# ET-power.net
KiCad netlist of a schematic drawn in Altium Designer
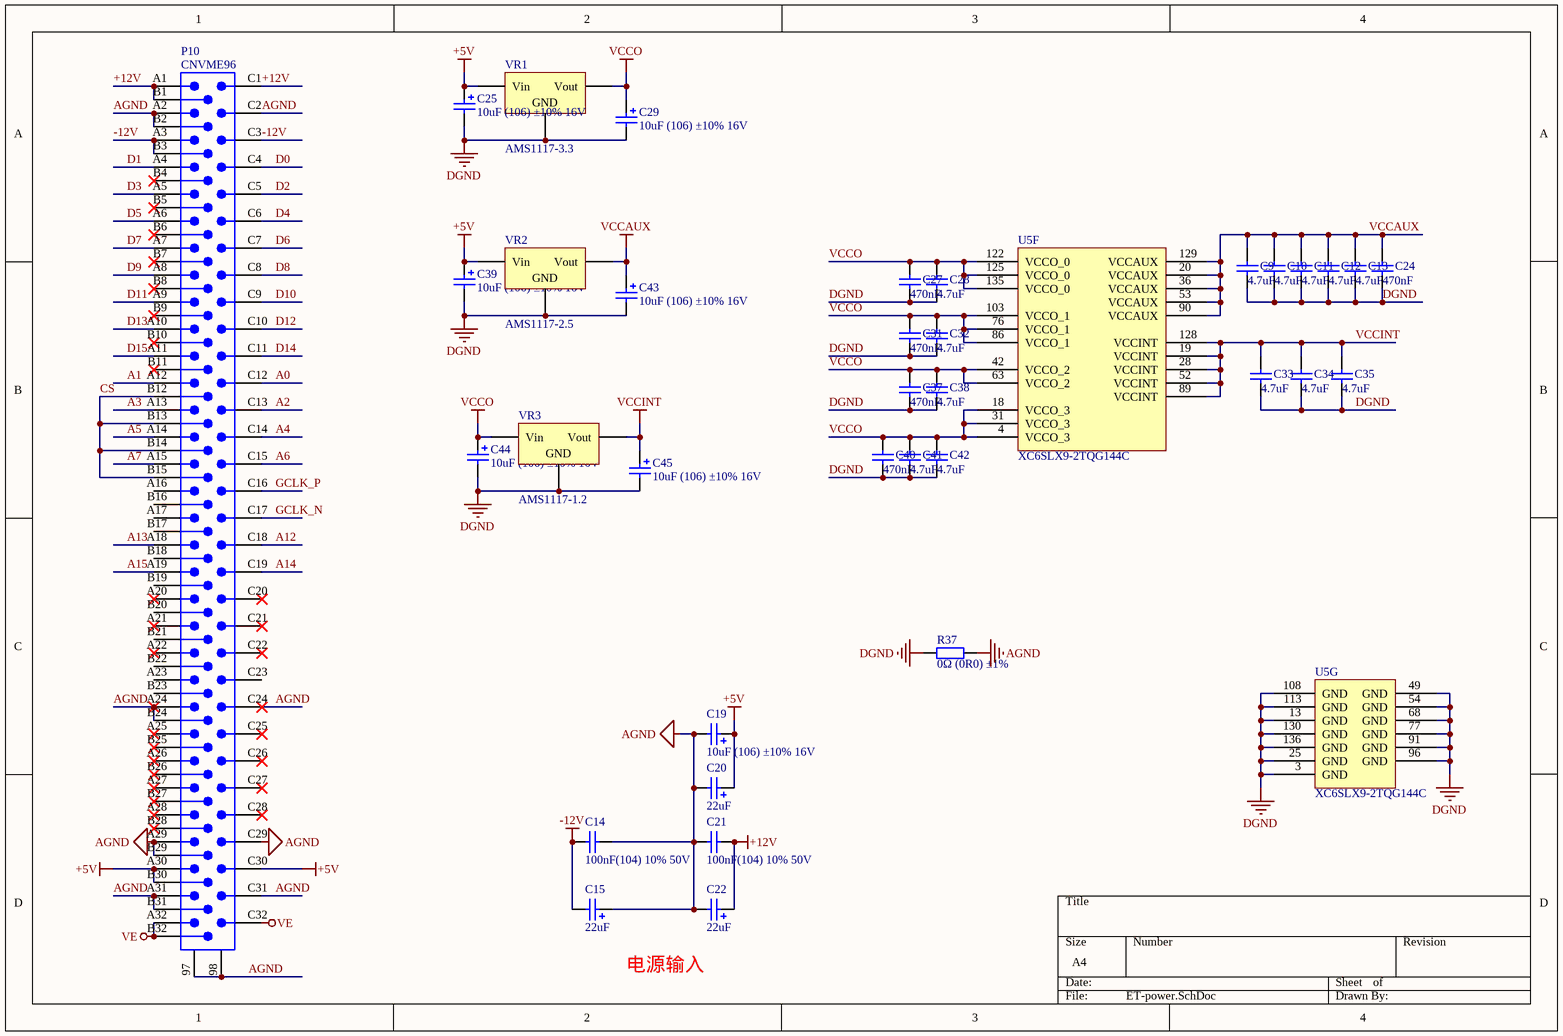
[diagram p0: ET-power.SchDoc]

(export (version "E")
  (design (tool "Eeschema 10.0.6"))
  (components
    (comp (ref "C9")
      (value "4.7uF")
      (footprint "LC-0805_C")
      (description "贴片电容")
      (libsource (lib "Miscellaneous Devices LC") (part "0805 4.7uF (475) 10% 25V"))
    )
    (comp (ref "C10")
      (value "4.7uF")
      (footprint "LC-0805_C")
      (description "贴片电容")
      (libsource (lib "Miscellaneous Devices LC") (part "0805 4.7uF (475) 10% 25V"))
    )
    (comp (ref "C11")
      (value "4.7uF")
      (footprint "LC-0805_C")
      (description "贴片电容")
      (libsource (lib "Miscellaneous Devices LC") (part "0805 4.7uF (475) 10% 25V"))
    )
    (comp (ref "C12")
      (value "4.7uF")
      (footprint "LC-0805_C")
      (description "贴片电容")
      (libsource (lib "Miscellaneous Devices LC") (part "0805 4.7uF (475) 10% 25V"))
    )
    (comp (ref "C13")
      (value "4.7uF")
      (footprint "LC-0805_C")
      (description "贴片电容")
      (libsource (lib "Miscellaneous Devices LC") (part "0805 4.7uF (475) 10% 25V"))
    )
    (comp (ref "C14")
      (value "100nF(104) 10% 50V")
      (footprint "LC-0805_C")
      (description "贴片电容")
      (libsource (lib "Miscellaneous Devices LC") (part "0805 100nF(104) 10% 50V"))
    )
    (comp (ref "C15") (value "22uF") (footprint "CASE-E_7343") (libsource (lib "钽电容") (part "钽电容")))
    (comp (ref "C19")
      (value "10uF (106) ±10% 16V")
      (footprint "LC-CASE-A_3216")
      (description "钽电容")
      (libsource (lib "Miscellaneous Devices LC") (part "3216 10uF (106) 10% 16V"))
    )
    (comp (ref "C20") (value "22uF") (footprint "CASE-E_7343") (libsource (lib "钽电容") (part "钽电容")))
    (comp (ref "C21")
      (value "100nF(104) 10% 50V")
      (footprint "LC-0805_C")
      (description "贴片电容")
      (libsource (lib "Miscellaneous Devices LC") (part "0805 100nF(104) 10% 50V"))
    )
    (comp (ref "C22") (value "22uF") (footprint "CASE-E_7343") (libsource (lib "钽电容") (part "钽电容")))
    (comp (ref "C24")
      (value "470nF")
      (footprint "LC-0805_C")
      (description "贴片电容")
      (libsource (lib "Miscellaneous Devices LC") (part "0805 470nF (474) 10% 50V"))
    )
    (comp (ref "C25")
      (value "10uF (106) ±10% 16V")
      (footprint "LC-CASE-A_3216")
      (description "钽电容")
      (libsource (lib "Miscellaneous Devices LC") (part "3216 10uF (106) 10% 16V"))
    )
    (comp (ref "C27")
      (value "470nF")
      (footprint "LC-0805_C")
      (description "贴片电容")
      (libsource (lib "Miscellaneous Devices LC") (part "0805 470nF (474) 10% 50V"))
    )
    (comp (ref "C28")
      (value "4.7uF")
      (footprint "LC-0805_C")
      (description "贴片电容")
      (libsource (lib "Miscellaneous Devices LC") (part "0805 4.7uF (475) 10% 25V"))
    )
    (comp (ref "C29")
      (value "10uF (106) ±10% 16V")
      (footprint "LC-CASE-A_3216")
      (description "钽电容")
      (libsource (lib "Miscellaneous Devices LC") (part "3216 10uF (106) 10% 16V"))
    )
    (comp (ref "C31")
      (value "470nF")
      (footprint "LC-0805_C")
      (description "贴片电容")
      (libsource (lib "Miscellaneous Devices LC") (part "0805 470nF (474) 10% 50V"))
    )
    (comp (ref "C32")
      (value "4.7uF")
      (footprint "LC-0805_C")
      (description "贴片电容")
      (libsource (lib "Miscellaneous Devices LC") (part "0805 4.7uF (475) 10% 25V"))
    )
    (comp (ref "C33")
      (value "4.7uF")
      (footprint "LC-0805_C")
      (description "贴片电容")
      (libsource (lib "Miscellaneous Devices LC") (part "0805 4.7uF (475) 10% 25V"))
    )
    (comp (ref "C34")
      (value "4.7uF")
      (footprint "LC-0805_C")
      (description "贴片电容")
      (libsource (lib "Miscellaneous Devices LC") (part "0805 4.7uF (475) 10% 25V"))
    )
    (comp (ref "C35")
      (value "4.7uF")
      (footprint "LC-0805_C")
      (description "贴片电容")
      (libsource (lib "Miscellaneous Devices LC") (part "0805 4.7uF (475) 10% 25V"))
    )
    (comp (ref "C37")
      (value "470nF")
      (footprint "LC-0805_C")
      (description "贴片电容")
      (libsource (lib "Miscellaneous Devices LC") (part "0805 470nF (474) 10% 50V"))
    )
    (comp (ref "C38")
      (value "4.7uF")
      (footprint "LC-0805_C")
      (description "贴片电容")
      (libsource (lib "Miscellaneous Devices LC") (part "0805 4.7uF (475) 10% 25V"))
    )
    (comp (ref "C39")
      (value "10uF (106) ±10% 16V")
      (footprint "LC-CASE-A_3216")
      (description "钽电容")
      (libsource (lib "Miscellaneous Devices LC") (part "3216 10uF (106) 10% 16V"))
    )
    (comp (ref "C40")
      (value "470nF")
      (footprint "LC-0805_C")
      (description "贴片电容")
      (libsource (lib "Miscellaneous Devices LC") (part "0805 470nF (474) 10% 50V"))
    )
    (comp (ref "C41")
      (value "4.7uF")
      (footprint "LC-0805_C")
      (description "贴片电容")
      (libsource (lib "Miscellaneous Devices LC") (part "0805 4.7uF (475) 10% 25V"))
    )
    (comp (ref "C42")
      (value "4.7uF")
      (footprint "LC-0805_C")
      (description "贴片电容")
      (libsource (lib "Miscellaneous Devices LC") (part "0805 4.7uF (475) 10% 25V"))
    )
    (comp (ref "C43")
      (value "10uF (106) ±10% 16V")
      (footprint "LC-CASE-A_3216")
      (description "钽电容")
      (libsource (lib "Miscellaneous Devices LC") (part "3216 10uF (106) 10% 16V"))
    )
    (comp (ref "C44")
      (value "10uF (106) ±10% 16V")
      (footprint "LC-CASE-A_3216")
      (description "钽电容")
      (libsource (lib "Miscellaneous Devices LC") (part "3216 10uF (106) 10% 16V"))
    )
    (comp (ref "C45")
      (value "10uF (106) ±10% 16V")
      (footprint "LC-CASE-A_3216")
      (description "钽电容")
      (libsource (lib "Miscellaneous Devices LC") (part "3216 10uF (106) 10% 16V"))
    )
    (comp (ref "P10")
      (value "CNVME96")
      (footprint "CNVME96")
      (description "96-Pin Connector (3x32 2.54mm grid)")
      (libsource (lib "*") (part "CNVME96"))
    )
    (comp (ref "R37")
      (value "0Ω (0R0) ±1%")
      (footprint "LC-0805_R")
      (description "贴片电阻")
      (libsource (lib "Miscellaneous Devices LC") (part "0805 0Ω (0R0) 1%"))
    )
    (comp (ref "U5")
      (value "XC6SLX9-2TQG144C")
      (footprint "TQG144_N")
      (fields (field (name "PUBLISHER") "Altium Limited"))
      (libsource (lib "Xilinx Spartan-6") (part "XC6SLX9-2TQG144C"))
    )
    (comp (ref "VR1")
      (value "AMS1117-3.3")
      (footprint "LC-SOT-223")
      (description "低压差线性稳压(LDO)")
      (libsource (lib "Miscellaneous Devices LC") (part "SOT-223 AMS1117-3.3"))
    )
    (comp (ref "VR2")
      (value "AMS1117-2.5")
      (footprint "LC-SOT-223")
      (description "低压差线性稳压(LDO)")
      (libsource (lib "AMS1117-2.5") (part "SOT-223 AMS1117-2.5"))
    )
    (comp (ref "VR3")
      (value "AMS1117-1.2")
      (footprint "LC-SOT-223")
      (description "低压差线性稳压(LDO)")
      (libsource (lib "AMS1117-1.2") (part "SOT-223 AMS1117-1.2"))
    )
  )
  (nets
    (net (code "1") (name "+5V") (class "Default")
      (node (ref "C19") (pin "1") (pinfunction "1_1") (pintype "passive"))
      (node (ref "C20") (pin "1") (pinfunction "1_1") (pintype "passive"))
      (node (ref "C25") (pin "1") (pinfunction "1_1") (pintype "passive"))
      (node (ref "C39") (pin "1") (pinfunction "1_1") (pintype "passive"))
      (node (ref "P10") (pin "A30") (pinfunction "A30_A30") (pintype "passive"))
      (node (ref "P10") (pin "B30") (pinfunction "B30_B30") (pintype "passive"))
      (node (ref "P10") (pin "C30") (pinfunction "C30_C30") (pintype "passive"))
      (node (ref "VR1") (pin "3") (pinfunction "Vin_3") (pintype "passive"))
      (node (ref "VR2") (pin "3") (pinfunction "Vin_3") (pintype "passive"))
    )
    (net (code "2") (name "+12V") (class "Default")
      (node (ref "C21") (pin "2") (pinfunction "2_2") (pintype "passive"))
      (node (ref "C22") (pin "1") (pinfunction "1_1") (pintype "passive"))
      (node (ref "P10") (pin "A1") (pinfunction "A1_A1") (pintype "passive"))
      (node (ref "P10") (pin "B1") (pinfunction "B1_B1") (pintype "passive"))
      (node (ref "P10") (pin "C1") (pinfunction "C1_C1") (pintype "passive"))
    )
    (net (code "3") (name "-12V") (class "Default")
      (node (ref "C14") (pin "1") (pinfunction "1_1") (pintype "passive"))
      (node (ref "C15") (pin "2") (pinfunction "2_2") (pintype "passive"))
      (node (ref "P10") (pin "A3") (pinfunction "A3_A3") (pintype "passive"))
      (node (ref "P10") (pin "B3") (pinfunction "B3_B3") (pintype "passive"))
      (node (ref "P10") (pin "C3") (pinfunction "C3_C3") (pintype "passive"))
    )
    (net (code "4") (name "/A0") (class "Default")
      (node (ref "P10") (pin "C12") (pinfunction "C12_C12") (pintype "passive"))
    )
    (net (code "5") (name "/A1") (class "Default")
      (node (ref "P10") (pin "A12") (pinfunction "A12_A12") (pintype "passive"))
    )
    (net (code "6") (name "/A2") (class "Default")
      (node (ref "P10") (pin "C13") (pinfunction "C13_C13") (pintype "passive"))
    )
    (net (code "7") (name "/A3") (class "Default")
      (node (ref "P10") (pin "A13") (pinfunction "A13_A13") (pintype "passive"))
    )
    (net (code "8") (name "/A4") (class "Default")
      (node (ref "P10") (pin "C14") (pinfunction "C14_C14") (pintype "passive"))
    )
    (net (code "9") (name "/A5") (class "Default")
      (node (ref "P10") (pin "A14") (pinfunction "A14_A14") (pintype "passive"))
    )
    (net (code "10") (name "/A6") (class "Default")
      (node (ref "P10") (pin "C15") (pinfunction "C15_C15") (pintype "passive"))
    )
    (net (code "11") (name "/A7") (class "Default")
      (node (ref "P10") (pin "A15") (pinfunction "A15_A15") (pintype "passive"))
    )
    (net (code "12") (name "/A12") (class "Default")
      (node (ref "P10") (pin "C18") (pinfunction "C18_C18") (pintype "passive"))
    )
    (net (code "13") (name "/A13") (class "Default")
      (node (ref "P10") (pin "A18") (pinfunction "A18_A18") (pintype "passive"))
    )
    (net (code "14") (name "/A14") (class "Default")
      (node (ref "P10") (pin "C19") (pinfunction "C19_C19") (pintype "passive"))
    )
    (net (code "15") (name "/A15") (class "Default")
      (node (ref "P10") (pin "A19") (pinfunction "A19_A19") (pintype "passive"))
    )
    (net (code "16") (name "/CS") (class "Default")
      (node (ref "P10") (pin "B12") (pinfunction "B12_B12") (pintype "passive"))
      (node (ref "P10") (pin "B13") (pinfunction "B13_B13") (pintype "passive"))
      (node (ref "P10") (pin "B14") (pinfunction "B14_B14") (pintype "passive"))
      (node (ref "P10") (pin "B15") (pinfunction "B15_B15") (pintype "passive"))
    )
    (net (code "17") (name "/D0") (class "Default")
      (node (ref "P10") (pin "C4") (pinfunction "C4_C4") (pintype "passive"))
    )
    (net (code "18") (name "/D1") (class "Default")
      (node (ref "P10") (pin "A4") (pinfunction "A4_A4") (pintype "passive"))
    )
    (net (code "19") (name "/D2") (class "Default")
      (node (ref "P10") (pin "C5") (pinfunction "C5_C5") (pintype "passive"))
    )
    (net (code "20") (name "/D3") (class "Default")
      (node (ref "P10") (pin "A5") (pinfunction "A5_A5") (pintype "passive"))
    )
    (net (code "21") (name "/D4") (class "Default")
      (node (ref "P10") (pin "C6") (pinfunction "C6_C6") (pintype "passive"))
    )
    (net (code "22") (name "/D5") (class "Default")
      (node (ref "P10") (pin "A6") (pinfunction "A6_A6") (pintype "passive"))
    )
    (net (code "23") (name "/D6") (class "Default")
      (node (ref "P10") (pin "C7") (pinfunction "C7_C7") (pintype "passive"))
    )
    (net (code "24") (name "/D7") (class "Default")
      (node (ref "P10") (pin "A7") (pinfunction "A7_A7") (pintype "passive"))
    )
    (net (code "25") (name "/D8") (class "Default")
      (node (ref "P10") (pin "C8") (pinfunction "C8_C8") (pintype "passive"))
    )
    (net (code "26") (name "/D9") (class "Default")
      (node (ref "P10") (pin "A8") (pinfunction "A8_A8") (pintype "passive"))
    )
    (net (code "27") (name "/D10") (class "Default")
      (node (ref "P10") (pin "C9") (pinfunction "C9_C9") (pintype "passive"))
    )
    (net (code "28") (name "/D11") (class "Default")
      (node (ref "P10") (pin "A9") (pinfunction "A9_A9") (pintype "passive"))
    )
    (net (code "29") (name "/D12") (class "Default")
      (node (ref "P10") (pin "C10") (pinfunction "C10_C10") (pintype "passive"))
    )
    (net (code "30") (name "/D13") (class "Default")
      (node (ref "P10") (pin "A10") (pinfunction "A10_A10") (pintype "passive"))
    )
    (net (code "31") (name "/D14") (class "Default")
      (node (ref "P10") (pin "C11") (pinfunction "C11_C11") (pintype "passive"))
    )
    (net (code "32") (name "/D15") (class "Default")
      (node (ref "P10") (pin "A11") (pinfunction "A11_A11") (pintype "passive"))
    )
    (net (code "33") (name "/GCLK_N") (class "Default")
      (node (ref "P10") (pin "C17") (pinfunction "C17_C17") (pintype "passive"))
    )
    (net (code "34") (name "/GCLK_P") (class "Default")
      (node (ref "P10") (pin "C16") (pinfunction "C16_C16") (pintype "passive"))
    )
    (net (code "35") (name "AGND") (class "Default")
      (node (ref "C14") (pin "2") (pinfunction "2_2") (pintype "passive"))
      (node (ref "C15") (pin "1") (pinfunction "1_1") (pintype "passive"))
      (node (ref "C19") (pin "2") (pinfunction "2_2") (pintype "passive"))
      (node (ref "C20") (pin "2") (pinfunction "2_2") (pintype "passive"))
      (node (ref "C21") (pin "1") (pinfunction "1_1") (pintype "passive"))
      (node (ref "C22") (pin "2") (pinfunction "2_2") (pintype "passive"))
      (node (ref "P10") (pin "97") (pinfunction "97_97") (pintype "passive"))
      (node (ref "P10") (pin "98") (pinfunction "98_98") (pintype "passive"))
      (node (ref "P10") (pin "A2") (pinfunction "A2_A2") (pintype "passive"))
      (node (ref "P10") (pin "A24") (pinfunction "A24_A24") (pintype "passive"))
      (node (ref "P10") (pin "A29") (pinfunction "A29_A29") (pintype "passive"))
      (node (ref "P10") (pin "A31") (pinfunction "A31_A31") (pintype "passive"))
      (node (ref "P10") (pin "B2") (pinfunction "B2_B2") (pintype "passive"))
      (node (ref "P10") (pin "B24") (pinfunction "B24_B24") (pintype "passive"))
      (node (ref "P10") (pin "B29") (pinfunction "B29_B29") (pintype "passive"))
      (node (ref "P10") (pin "B31") (pinfunction "B31_B31") (pintype "passive"))
      (node (ref "P10") (pin "C2") (pinfunction "C2_C2") (pintype "passive"))
      (node (ref "P10") (pin "C24") (pinfunction "C24_C24") (pintype "passive"))
      (node (ref "P10") (pin "C29") (pinfunction "C29_C29") (pintype "passive"))
      (node (ref "P10") (pin "C31") (pinfunction "C31_C31") (pintype "passive"))
      (node (ref "R37") (pin "2") (pinfunction "2_2") (pintype "passive"))
    )
    (net (code "36") (name "DGND") (class "Default")
      (node (ref "C10") (pin "1") (pinfunction "1_1") (pintype "passive"))
      (node (ref "C11") (pin "1") (pinfunction "1_1") (pintype "passive"))
      (node (ref "C12") (pin "1") (pinfunction "1_1") (pintype "passive"))
      (node (ref "C13") (pin "1") (pinfunction "1_1") (pintype "passive"))
      (node (ref "C24") (pin "1") (pinfunction "1_1") (pintype "passive"))
      (node (ref "C25") (pin "2") (pinfunction "2_2") (pintype "passive"))
      (node (ref "C27") (pin "1") (pinfunction "1_1") (pintype "passive"))
      (node (ref "C28") (pin "1") (pinfunction "1_1") (pintype "passive"))
      (node (ref "C29") (pin "2") (pinfunction "2_2") (pintype "passive"))
      (node (ref "C31") (pin "1") (pinfunction "1_1") (pintype "passive"))
      (node (ref "C32") (pin "1") (pinfunction "1_1") (pintype "passive"))
      (node (ref "C33") (pin "1") (pinfunction "1_1") (pintype "passive"))
      (node (ref "C34") (pin "1") (pinfunction "1_1") (pintype "passive"))
      (node (ref "C35") (pin "1") (pinfunction "1_1") (pintype "passive"))
      (node (ref "C37") (pin "1") (pinfunction "1_1") (pintype "passive"))
      (node (ref "C38") (pin "1") (pinfunction "1_1") (pintype "passive"))
      (node (ref "C39") (pin "2") (pinfunction "2_2") (pintype "passive"))
      (node (ref "C40") (pin "1") (pinfunction "1_1") (pintype "passive"))
      (node (ref "C41") (pin "1") (pinfunction "1_1") (pintype "passive"))
      (node (ref "C42") (pin "1") (pinfunction "1_1") (pintype "passive"))
      (node (ref "C43") (pin "2") (pinfunction "2_2") (pintype "passive"))
      (node (ref "C44") (pin "2") (pinfunction "2_2") (pintype "passive"))
      (node (ref "C45") (pin "2") (pinfunction "2_2") (pintype "passive"))
      (node (ref "C9") (pin "1") (pinfunction "1_1") (pintype "passive"))
      (node (ref "R37") (pin "1") (pinfunction "1_1") (pintype "passive"))
      (node (ref "U5") (pin "108") (pinfunction "GND_108") (pintype "power_in"))
      (node (ref "U5") (pin "113") (pinfunction "GND_113") (pintype "power_in"))
      (node (ref "U5") (pin "13") (pinfunction "GND_13") (pintype "power_in"))
      (node (ref "U5") (pin "130") (pinfunction "GND_130") (pintype "power_in"))
      (node (ref "U5") (pin "136") (pinfunction "GND_136") (pintype "power_in"))
      (node (ref "U5") (pin "25") (pinfunction "GND_25") (pintype "power_in"))
      (node (ref "U5") (pin "3") (pinfunction "GND_3") (pintype "power_in"))
      (node (ref "U5") (pin "49") (pinfunction "GND_49") (pintype "power_in"))
      (node (ref "U5") (pin "54") (pinfunction "GND_54") (pintype "power_in"))
      (node (ref "U5") (pin "68") (pinfunction "GND_68") (pintype "power_in"))
      (node (ref "U5") (pin "77") (pinfunction "GND_77") (pintype "power_in"))
      (node (ref "U5") (pin "91") (pinfunction "GND_91") (pintype "power_in"))
      (node (ref "U5") (pin "96") (pinfunction "GND_96") (pintype "power_in"))
      (node (ref "VR1") (pin "1") (pinfunction "GND_1") (pintype "passive"))
      (node (ref "VR2") (pin "1") (pinfunction "GND_1") (pintype "passive"))
      (node (ref "VR3") (pin "1") (pinfunction "GND_1") (pintype "passive"))
    )
    (net (code "37") (name "VCCAUX") (class "Default")
      (node (ref "C10") (pin "2") (pinfunction "2_2") (pintype "passive"))
      (node (ref "C11") (pin "2") (pinfunction "2_2") (pintype "passive"))
      (node (ref "C12") (pin "2") (pinfunction "2_2") (pintype "passive"))
      (node (ref "C13") (pin "2") (pinfunction "2_2") (pintype "passive"))
      (node (ref "C24") (pin "2") (pinfunction "2_2") (pintype "passive"))
      (node (ref "C43") (pin "1") (pinfunction "1_1") (pintype "passive"))
      (node (ref "C9") (pin "2") (pinfunction "2_2") (pintype "passive"))
      (node (ref "U5") (pin "129") (pinfunction "VCCAUX_129") (pintype "power_in"))
      (node (ref "U5") (pin "20") (pinfunction "VCCAUX_20") (pintype "power_in"))
      (node (ref "U5") (pin "36") (pinfunction "VCCAUX_36") (pintype "power_in"))
      (node (ref "U5") (pin "53") (pinfunction "VCCAUX_53") (pintype "power_in"))
      (node (ref "U5") (pin "90") (pinfunction "VCCAUX_90") (pintype "power_in"))
      (node (ref "VR2") (pin "2") (pinfunction "Vout_2") (pintype "passive"))
    )
    (net (code "38") (name "VCCINT") (class "Default")
      (node (ref "C33") (pin "2") (pinfunction "2_2") (pintype "passive"))
      (node (ref "C34") (pin "2") (pinfunction "2_2") (pintype "passive"))
      (node (ref "C35") (pin "2") (pinfunction "2_2") (pintype "passive"))
      (node (ref "C45") (pin "1") (pinfunction "1_1") (pintype "passive"))
      (node (ref "U5") (pin "128") (pinfunction "VCCINT_128") (pintype "power_in"))
      (node (ref "U5") (pin "19") (pinfunction "VCCINT_19") (pintype "power_in"))
      (node (ref "U5") (pin "28") (pinfunction "VCCINT_28") (pintype "power_in"))
      (node (ref "U5") (pin "52") (pinfunction "VCCINT_52") (pintype "power_in"))
      (node (ref "U5") (pin "89") (pinfunction "VCCINT_89") (pintype "power_in"))
      (node (ref "VR3") (pin "2") (pinfunction "Vout_2") (pintype "passive"))
    )
    (net (code "39") (name "VCCO") (class "Default")
      (node (ref "C27") (pin "2") (pinfunction "2_2") (pintype "passive"))
      (node (ref "C28") (pin "2") (pinfunction "2_2") (pintype "passive"))
      (node (ref "C29") (pin "1") (pinfunction "1_1") (pintype "passive"))
      (node (ref "C31") (pin "2") (pinfunction "2_2") (pintype "passive"))
      (node (ref "C32") (pin "2") (pinfunction "2_2") (pintype "passive"))
      (node (ref "C37") (pin "2") (pinfunction "2_2") (pintype "passive"))
      (node (ref "C38") (pin "2") (pinfunction "2_2") (pintype "passive"))
      (node (ref "C40") (pin "2") (pinfunction "2_2") (pintype "passive"))
      (node (ref "C41") (pin "2") (pinfunction "2_2") (pintype "passive"))
      (node (ref "C42") (pin "2") (pinfunction "2_2") (pintype "passive"))
      (node (ref "C44") (pin "1") (pinfunction "1_1") (pintype "passive"))
      (node (ref "U5") (pin "103") (pinfunction "VCCO_1_103") (pintype "power_in"))
      (node (ref "U5") (pin "122") (pinfunction "VCCO_0_122") (pintype "power_in"))
      (node (ref "U5") (pin "125") (pinfunction "VCCO_0_125") (pintype "power_in"))
      (node (ref "U5") (pin "135") (pinfunction "VCCO_0_135") (pintype "power_in"))
      (node (ref "U5") (pin "18") (pinfunction "VCCO_3_18") (pintype "power_in"))
      (node (ref "U5") (pin "31") (pinfunction "VCCO_3_31") (pintype "power_in"))
      (node (ref "U5") (pin "4") (pinfunction "VCCO_3_4") (pintype "power_in"))
      (node (ref "U5") (pin "42") (pinfunction "VCCO_2_42") (pintype "power_in"))
      (node (ref "U5") (pin "63") (pinfunction "VCCO_2_63") (pintype "power_in"))
      (node (ref "U5") (pin "76") (pinfunction "VCCO_1_76") (pintype "power_in"))
      (node (ref "U5") (pin "86") (pinfunction "VCCO_1_86") (pintype "power_in"))
      (node (ref "VR1") (pin "2") (pinfunction "Vout_2") (pintype "passive"))
      (node (ref "VR3") (pin "3") (pinfunction "Vin_3") (pintype "passive"))
    )
    (net (code "40") (name "VE") (class "Default")
      (node (ref "P10") (pin "A32") (pinfunction "A32_A32") (pintype "passive"))
      (node (ref "P10") (pin "B32") (pinfunction "B32_B32") (pintype "passive"))
      (node (ref "P10") (pin "C32") (pinfunction "C32_C32") (pintype "passive"))
    )
    (net (code "41") (name "unconnected-(P10-PadA16)") (class "Default")
      (node (ref "P10") (pin "A16") (pinfunction "A16_A16") (pintype "passive"))
    )
    (net (code "42") (name "unconnected-(P10-PadA17)") (class "Default")
      (node (ref "P10") (pin "A17") (pinfunction "A17_A17") (pintype "passive"))
    )
    (net (code "43") (name "unconnected-(P10-PadA20)") (class "Default")
      (node (ref "P10") (pin "A20") (pinfunction "A20_A20") (pintype "passive+no_connect"))
    )
    (net (code "44") (name "unconnected-(P10-PadA21)") (class "Default")
      (node (ref "P10") (pin "A21") (pinfunction "A21_A21") (pintype "passive+no_connect"))
    )
    (net (code "45") (name "unconnected-(P10-PadA22)") (class "Default")
      (node (ref "P10") (pin "A22") (pinfunction "A22_A22") (pintype "passive+no_connect"))
    )
    (net (code "46") (name "unconnected-(P10-PadA23)") (class "Default")
      (node (ref "P10") (pin "A23") (pinfunction "A23_A23") (pintype "passive"))
    )
    (net (code "47") (name "unconnected-(P10-PadA25)") (class "Default")
      (node (ref "P10") (pin "A25") (pinfunction "A25_A25") (pintype "passive+no_connect"))
    )
    (net (code "48") (name "unconnected-(P10-PadA26)") (class "Default")
      (node (ref "P10") (pin "A26") (pinfunction "A26_A26") (pintype "passive+no_connect"))
    )
    (net (code "49") (name "unconnected-(P10-PadA27)") (class "Default")
      (node (ref "P10") (pin "A27") (pinfunction "A27_A27") (pintype "passive+no_connect"))
    )
    (net (code "50") (name "unconnected-(P10-PadA28)") (class "Default")
      (node (ref "P10") (pin "A28") (pinfunction "A28_A28") (pintype "passive+no_connect"))
    )
    (net (code "51") (name "unconnected-(P10-PadB4)") (class "Default")
      (node (ref "P10") (pin "B4") (pinfunction "B4_B4") (pintype "passive+no_connect"))
    )
    (net (code "52") (name "unconnected-(P10-PadB5)") (class "Default")
      (node (ref "P10") (pin "B5") (pinfunction "B5_B5") (pintype "passive+no_connect"))
    )
    (net (code "53") (name "unconnected-(P10-PadB6)") (class "Default")
      (node (ref "P10") (pin "B6") (pinfunction "B6_B6") (pintype "passive+no_connect"))
    )
    (net (code "54") (name "unconnected-(P10-PadB7)") (class "Default")
      (node (ref "P10") (pin "B7") (pinfunction "B7_B7") (pintype "passive+no_connect"))
    )
    (net (code "55") (name "unconnected-(P10-PadB8)") (class "Default")
      (node (ref "P10") (pin "B8") (pinfunction "B8_B8") (pintype "passive+no_connect"))
    )
    (net (code "56") (name "unconnected-(P10-PadB9)") (class "Default")
      (node (ref "P10") (pin "B9") (pinfunction "B9_B9") (pintype "passive+no_connect"))
    )
    (net (code "57") (name "unconnected-(P10-PadB10)") (class "Default")
      (node (ref "P10") (pin "B10") (pinfunction "B10_B10") (pintype "passive+no_connect"))
    )
    (net (code "58") (name "unconnected-(P10-PadB11)") (class "Default")
      (node (ref "P10") (pin "B11") (pinfunction "B11_B11") (pintype "passive+no_connect"))
    )
    (net (code "59") (name "unconnected-(P10-PadB16)") (class "Default")
      (node (ref "P10") (pin "B16") (pinfunction "B16_B16") (pintype "passive"))
    )
    (net (code "60") (name "unconnected-(P10-PadB17)") (class "Default")
      (node (ref "P10") (pin "B17") (pinfunction "B17_B17") (pintype "passive"))
    )
    (net (code "61") (name "unconnected-(P10-PadB18)") (class "Default")
      (node (ref "P10") (pin "B18") (pinfunction "B18_B18") (pintype "passive"))
    )
    (net (code "62") (name "unconnected-(P10-PadB19)") (class "Default")
      (node (ref "P10") (pin "B19") (pinfunction "B19_B19") (pintype "passive"))
    )
    (net (code "63") (name "unconnected-(P10-PadB20)") (class "Default")
      (node (ref "P10") (pin "B20") (pinfunction "B20_B20") (pintype "passive"))
    )
    (net (code "64") (name "unconnected-(P10-PadB21)") (class "Default")
      (node (ref "P10") (pin "B21") (pinfunction "B21_B21") (pintype "passive"))
    )
    (net (code "65") (name "unconnected-(P10-PadB22)") (class "Default")
      (node (ref "P10") (pin "B22") (pinfunction "B22_B22") (pintype "passive"))
    )
    (net (code "66") (name "unconnected-(P10-PadB23)") (class "Default")
      (node (ref "P10") (pin "B23") (pinfunction "B23_B23") (pintype "passive"))
    )
    (net (code "67") (name "unconnected-(P10-PadB25)") (class "Default")
      (node (ref "P10") (pin "B25") (pinfunction "B25_B25") (pintype "passive+no_connect"))
    )
    (net (code "68") (name "unconnected-(P10-PadB26)") (class "Default")
      (node (ref "P10") (pin "B26") (pinfunction "B26_B26") (pintype "passive+no_connect"))
    )
    (net (code "69") (name "unconnected-(P10-PadB27)") (class "Default")
      (node (ref "P10") (pin "B27") (pinfunction "B27_B27") (pintype "passive+no_connect"))
    )
    (net (code "70") (name "unconnected-(P10-PadB28)") (class "Default")
      (node (ref "P10") (pin "B28") (pinfunction "B28_B28") (pintype "passive+no_connect"))
    )
    (net (code "71") (name "unconnected-(P10-PadC20)") (class "Default")
      (node (ref "P10") (pin "C20") (pinfunction "C20_C20") (pintype "passive+no_connect"))
    )
    (net (code "72") (name "unconnected-(P10-PadC21)") (class "Default")
      (node (ref "P10") (pin "C21") (pinfunction "C21_C21") (pintype "passive+no_connect"))
    )
    (net (code "73") (name "unconnected-(P10-PadC22)") (class "Default")
      (node (ref "P10") (pin "C22") (pinfunction "C22_C22") (pintype "passive+no_connect"))
    )
    (net (code "74") (name "unconnected-(P10-PadC23)") (class "Default")
      (node (ref "P10") (pin "C23") (pinfunction "C23_C23") (pintype "passive"))
    )
    (net (code "75") (name "unconnected-(P10-PadC25)") (class "Default")
      (node (ref "P10") (pin "C25") (pinfunction "C25_C25") (pintype "passive+no_connect"))
    )
    (net (code "76") (name "unconnected-(P10-PadC26)") (class "Default")
      (node (ref "P10") (pin "C26") (pinfunction "C26_C26") (pintype "passive+no_connect"))
    )
    (net (code "77") (name "unconnected-(P10-PadC27)") (class "Default")
      (node (ref "P10") (pin "C27") (pinfunction "C27_C27") (pintype "passive+no_connect"))
    )
    (net (code "78") (name "unconnected-(P10-PadC28)") (class "Default")
      (node (ref "P10") (pin "C28") (pinfunction "C28_C28") (pintype "passive+no_connect"))
    )
  )
)
